# GNSS_MB.net
KiCad netlist of a schematic drawn in Altium Designer
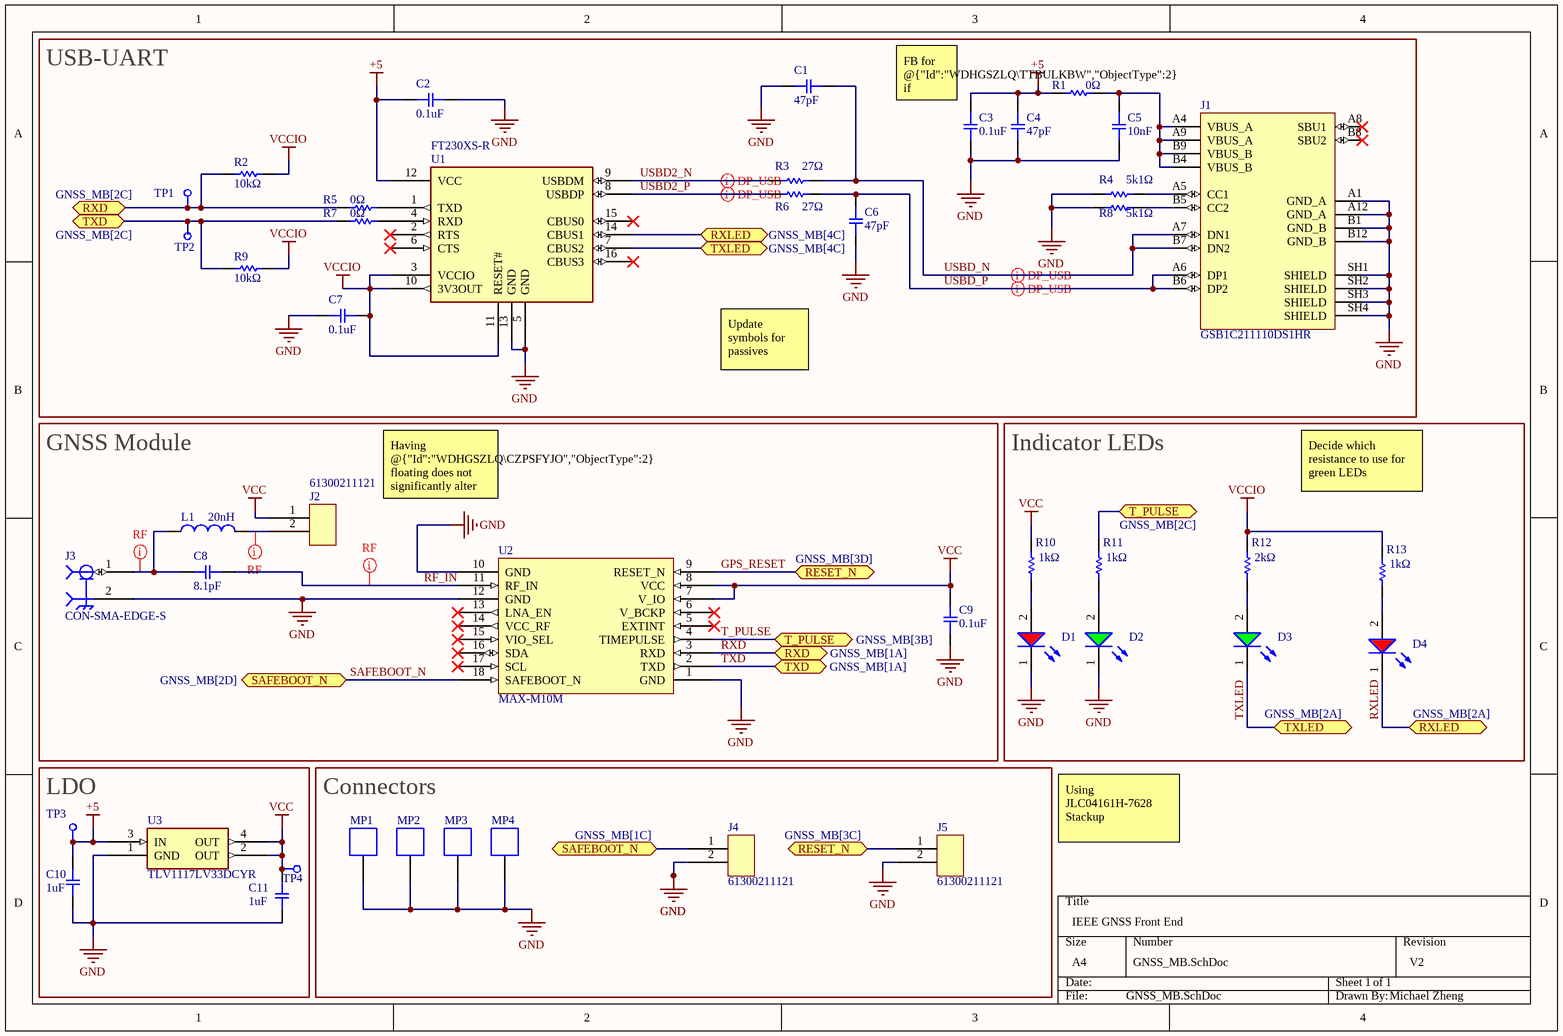
[diagram p0: GNSS_MB.SchDoc]

(export (version "E")
  (design (tool "Eeschema 10.0.6"))
  (components
    (comp (ref "C1")
      (value "GCM1885C2A470JA16D")
      (footprint "CAP_MURATA_0603")
      (description "CAP CER 47PF 100V C0G/NP0 0603")
      (fields (field (name "CAPACITANCE") "47pF"))
      (libsource (lib "Symbols") (part "GCM188L81H104KA57D"))
    )
    (comp (ref "C2")
      (value "GCM188L81H104KA57D")
      (footprint "CAP_MURATA_0603")
      (description "CAP CER 0.1UF 50V X8L 0603")
      (fields (field (name "CAPACITANCE") "0.1uF"))
      (libsource (lib "Symbols") (part "GCM188L81H104KA57D"))
    )
    (comp (ref "C3")
      (value "GCM188L81H104KA57D")
      (footprint "CAP_MURATA_0603")
      (description "CAP CER 0.1UF 50V X8L 0603")
      (fields (field (name "CAPACITANCE") "0.1uF"))
      (libsource (lib "Symbols") (part "GCM188L81H104KA57D"))
    )
    (comp (ref "C4")
      (value "GCM1885C2A470JA16D")
      (footprint "CAP_MURATA_0603")
      (description "CAP CER 47PF 100V C0G/NP0 0603")
      (fields (field (name "CAPACITANCE") "47pF"))
      (libsource (lib "Symbols") (part "GCM188L81H104KA57D"))
    )
    (comp (ref "C5")
      (value "GCM188R72A103KA37D")
      (footprint "CAP_MURATA_0603")
      (description "CAP CER 10000PF 100V X7R 0603")
      (fields (field (name "CAPACITANCE") "10nF"))
      (libsource (lib "Symbols") (part "GCM188L81H104KA57D"))
    )
    (comp (ref "C6")
      (value "GCM1885C2A470JA16D")
      (footprint "CAP_MURATA_0603")
      (description "CAP CER 47PF 100V C0G/NP0 0603")
      (fields (field (name "CAPACITANCE") "47pF"))
      (libsource (lib "Symbols") (part "GCM188L81H104KA57D"))
    )
    (comp (ref "C7")
      (value "GCM188L81H104KA57D")
      (footprint "CAP_MURATA_0603")
      (description "CAP CER 0.1UF 50V X8L 0603")
      (fields (field (name "CAPACITANCE") "0.1uF"))
      (libsource (lib "Symbols") (part "GCM188L81H104KA57D"))
    )
    (comp (ref "C8")
      (value "GJM1555C1H8R1BB01D")
      (footprint "0402_CAP")
      (description "CAP CER 8.1PF 50V C0G/NP0 0402")
      (fields (field (name "CAPACITANCE") "8.1pF"))
      (libsource (lib "Symbols") (part "GRM1555C1H102JA01D"))
    )
    (comp (ref "C9")
      (value "GCM188L81H104KA57D")
      (footprint "CAP_MURATA_0603")
      (description "CAP CER 0.1UF 50V X8L 0603")
      (fields (field (name "CAPACITANCE") "0.1uF"))
      (libsource (lib "Symbols") (part "GCM188L81H104KA57D"))
    )
    (comp (ref "C10")
      (value "GRM188R61A105KA61D")
      (footprint "CAP_MURATA_0603")
      (description "CAP CER 1UF 10V X5R 0603")
      (fields (field (name "CAPACITANCE") "1uF"))
      (libsource (lib "Symbols") (part "GRM188R61A105KA61D"))
    )
    (comp (ref "C11")
      (value "GRM188R61A105KA61D")
      (footprint "CAP_MURATA_0603")
      (description "CAP CER 1UF 10V X5R 0603")
      (fields (field (name "CAPACITANCE") "1uF"))
      (libsource (lib "Symbols") (part "GRM188R61A105KA61D"))
    )
    (comp (ref "D1")
      (value "Red, 2V, 140°")
      (footprint "WL-SMCW")
      (description "WL-SMCW Mono-color Chip LED Waterclear, SMT, size 0603, Red, 2V, 140°")
      (fields
        (field (name "MANUFACTURER PART NUMBER") "150060RS75000")
        (field (name "MANUFACTURER") "Wurth Elektronik")
      )
      (libsource (lib "Symbols") (part "150060RS75000"))
    )
    (comp (ref "D2")
      (value "Green, 3.2V, 140°")
      (footprint "WL-SMCW")
      (description "WL-SMCW Mono-color Chip LED Waterclear, SMT, size 0603, Green, 3.2V, 140°")
      (fields
        (field (name "MANUFACTURER PART NUMBER") "150060GS75000")
        (field (name "MANUFACTURER") "Wurth Elektronik")
      )
      (libsource (lib "Symbols") (part "150060GS75000"))
    )
    (comp (ref "D3")
      (value "Green, 3.2V, 140°")
      (footprint "WL-SMCW")
      (description "WL-SMCW Mono-color Chip LED Waterclear, SMT, size 0603, Green, 3.2V, 140°")
      (fields
        (field (name "MANUFACTURER PART NUMBER") "150060GS75000")
        (field (name "MANUFACTURER") "Wurth Elektronik")
      )
      (libsource (lib "Symbols") (part "150060GS75000"))
    )
    (comp (ref "D4")
      (value "Red, 2V, 140°")
      (footprint "WL-SMCW")
      (description "WL-SMCW Mono-color Chip LED Waterclear, SMT, size 0603, Red, 2V, 140°")
      (fields
        (field (name "MANUFACTURER PART NUMBER") "150060RS75000")
        (field (name "MANUFACTURER") "Wurth Elektronik")
      )
      (libsource (lib "Symbols") (part "150060RS75000"))
    )
    (comp (ref "J1")
      (value "GSB1C211110DS1HR")
      (footprint "AMPHENOL_GSB1C211110DS1HR")
      (description "USB2.0, Type C, Top mount, Center Height 1.78mm, Dual Row DIP")
      (fields (field (name "MF") "Amphenol Canada"))
      (libsource (lib "Symbols") (part "GSB1C211110DS1HR"))
    )
    (comp (ref "J2")
      (value "61300211121")
      (footprint "61300211121")
      (description "CONN HEADER VERT 2POS 2.54MM")
      (libsource (lib "Symbols") (part "61300211121"))
    )
    (comp (ref "J3")
      (value "CON-SMA-EDGE-S")
      (footprint "RFSOLUTIONS_CON-SMA-EDGE-S")
      (description "CONN SMA JACK STR EDGE MNT")
      (libsource (lib "Symbols") (part "CON-SMA-EDGE-S"))
    )
    (comp (ref "J4")
      (value "61300211121")
      (footprint "61300211121")
      (description "CONN HEADER VERT 2POS 2.54MM")
      (libsource (lib "Symbols") (part "61300211121"))
    )
    (comp (ref "J5")
      (value "61300211121")
      (footprint "61300211121")
      (description "CONN HEADER VERT 2POS 2.54MM")
      (libsource (lib "Symbols") (part "61300211121"))
    )
    (comp (ref "L1")
      (value "20nH")
      (footprint "INDC1006X60N")
      (description "FIXED IND 20NH 800MA 0.186OHM SM")
      (fields (field (name "MP") "LQW15AN3N6C10D") (field (name "Comment") "LQW15AN20NG8ZD"))
      (libsource (lib "Symbols") (part "LQW15AN3N6C10D"))
    )
    (comp (ref "MP1")
      (value "36900000")
      (footprint "36900000")
      (description "WE-SHC Shielding Cabinet, Clip, Tin Plated, Tape and Reel, 6.5x0.8x1.27mm")
      (fields (field (name "MANUFACTURER") "Wurth Elektronik"))
      (libsource (lib "Symbols") (part "36900000"))
    )
    (comp (ref "MP2")
      (value "36900000")
      (footprint "36900000")
      (description "WE-SHC Shielding Cabinet, Clip, Tin Plated, Tape and Reel, 6.5x0.8x1.27mm")
      (fields (field (name "MANUFACTURER") "Wurth Elektronik"))
      (libsource (lib "Symbols") (part "36900000"))
    )
    (comp (ref "MP3")
      (value "36900000")
      (footprint "36900000")
      (description "WE-SHC Shielding Cabinet, Clip, Tin Plated, Tape and Reel, 6.5x0.8x1.27mm")
      (fields (field (name "MANUFACTURER") "Wurth Elektronik"))
      (libsource (lib "Symbols") (part "36900000"))
    )
    (comp (ref "MP4")
      (value "36900000")
      (footprint "36900000")
      (description "WE-SHC Shielding Cabinet, Clip, Tin Plated, Tape and Reel, 6.5x0.8x1.27mm")
      (fields (field (name "MANUFACTURER") "Wurth Elektronik"))
      (libsource (lib "Symbols") (part "36900000"))
    )
    (comp (ref "R1")
      (value "RC0603JR-070RL")
      (footprint "RC0603JR-070RL")
      (description "Chip Resistor, 0 Ohm, +/- 5%, 0.1 W, -55 to 155 degC, 0603 (1608 Metric), RoHS, Tape and Reel")
      (fields
        (field (name "TOLERANCE") "5%")
        (field (name "RESISTANCE") "0Ω")
        (field (name "MANUFACTURER") "Yageo")
      )
      (libsource (lib "Symbols") (part "RC0603JR-070RL"))
    )
    (comp (ref "R2")
      (value "RC0603FR-0710KL")
      (footprint "RC0603JR-070RL")
      (description "RES 10K OHM 1% 1/10W 0603")
      (fields
        (field (name "TOLERANCE") "5%")
        (field (name "RESISTANCE") "10kΩ")
        (field (name "MANUFACTURER") "Yageo")
      )
      (libsource (lib "Symbols") (part "RC0603JR-070RL"))
    )
    (comp (ref "R3")
      (value "RC0603FR-0727RL")
      (footprint "RC0603JR-070RL")
      (description "RES 27 OHM 1% 1/10W 0603")
      (fields
        (field (name "TOLERANCE") "5%")
        (field (name "RESISTANCE") "27Ω")
        (field (name "MANUFACTURER") "Yageo")
      )
      (libsource (lib "Symbols") (part "RC0603JR-070RL"))
    )
    (comp (ref "R4")
      (value "RC0603FR-075K1L")
      (footprint "RC0603JR-070RL")
      (description "RES 5.1K OHM 1% 1/10W 0603")
      (fields
        (field (name "TOLERANCE") "5%")
        (field (name "RESISTANCE") "5k1Ω")
        (field (name "MANUFACTURER") "Yageo")
      )
      (libsource (lib "Symbols") (part "RC0603JR-070RL"))
    )
    (comp (ref "R5")
      (value "RC0603JR-070RL")
      (footprint "RC0603JR-070RL")
      (description "Chip Resistor, 0 Ohm, +/- 5%, 0.1 W, -55 to 155 degC, 0603 (1608 Metric), RoHS, Tape and Reel")
      (fields
        (field (name "TOLERANCE") "5%")
        (field (name "RESISTANCE") "0Ω")
        (field (name "MANUFACTURER") "Yageo")
      )
      (libsource (lib "Symbols") (part "RC0603JR-070RL"))
    )
    (comp (ref "R6")
      (value "RC0603FR-0727RL")
      (footprint "RC0603JR-070RL")
      (description "RES 27 OHM 1% 1/10W 0603")
      (fields
        (field (name "TOLERANCE") "5%")
        (field (name "RESISTANCE") "27Ω")
        (field (name "MANUFACTURER") "Yageo")
      )
      (libsource (lib "Symbols") (part "RC0603JR-070RL"))
    )
    (comp (ref "R7")
      (value "RC0603JR-070RL")
      (footprint "RC0603JR-070RL")
      (description "Chip Resistor, 0 Ohm, +/- 5%, 0.1 W, -55 to 155 degC, 0603 (1608 Metric), RoHS, Tape and Reel")
      (fields
        (field (name "TOLERANCE") "5%")
        (field (name "RESISTANCE") "0Ω")
        (field (name "MANUFACTURER") "Yageo")
      )
      (libsource (lib "Symbols") (part "RC0603JR-070RL"))
    )
    (comp (ref "R8")
      (value "RC0603FR-075K1L")
      (footprint "RC0603JR-070RL")
      (description "RES 5.1K OHM 1% 1/10W 0603")
      (fields
        (field (name "TOLERANCE") "5%")
        (field (name "RESISTANCE") "5k1Ω")
        (field (name "MANUFACTURER") "Yageo")
      )
      (libsource (lib "Symbols") (part "RC0603JR-070RL"))
    )
    (comp (ref "R9")
      (value "RC0603FR-0710KL")
      (footprint "RC0603JR-070RL")
      (description "RES 10K OHM 1% 1/10W 0603")
      (fields
        (field (name "TOLERANCE") "5%")
        (field (name "RESISTANCE") "10kΩ")
        (field (name "MANUFACTURER") "Yageo")
      )
      (libsource (lib "Symbols") (part "RC0603JR-070RL"))
    )
    (comp (ref "R10")
      (value "RC0603FR-071KL")
      (footprint "RC0603JR-070RL")
      (description "1 kOhms ±1% 0.1W, 1/10W Chip Resistor 0603 (1608 Metric) Moisture Resistant Thick Film")
      (fields
        (field (name "TOLERANCE") "5%")
        (field (name "RESISTANCE") "1kΩ")
        (field (name "MANUFACTURER") "Yageo")
      )
      (libsource (lib "Symbols") (part "RC0603JR-070RL"))
    )
    (comp (ref "R11")
      (value "RC0603FR-071KL")
      (footprint "RC0603JR-070RL")
      (description "1 kOhms ±1% 0.1W, 1/10W Chip Resistor 0603 (1608 Metric) Moisture Resistant Thick Film")
      (fields
        (field (name "TOLERANCE") "5%")
        (field (name "RESISTANCE") "1kΩ")
        (field (name "MANUFACTURER") "Yageo")
      )
      (libsource (lib "Symbols") (part "RC0603JR-070RL"))
    )
    (comp (ref "R12")
      (value "RC0603JR-072KL")
      (footprint "RC0603JR-070RL")
      (description "2 kOhms ±5% 0.1W, 1/10W Chip Resistor 0603 (1608 Metric) Moisture Resistant Thick Film")
      (fields
        (field (name "TOLERANCE") "5%")
        (field (name "RESISTANCE") "2kΩ")
        (field (name "MANUFACTURER") "Yageo")
      )
      (libsource (lib "Symbols") (part "RC0603JR-070RL"))
    )
    (comp (ref "R13")
      (value "RC0603FR-071KL")
      (footprint "RC0603JR-070RL")
      (description "1 kOhms ±1% 0.1W, 1/10W Chip Resistor 0603 (1608 Metric) Moisture Resistant Thick Film")
      (fields
        (field (name "TOLERANCE") "5%")
        (field (name "RESISTANCE") "1kΩ")
        (field (name "MANUFACTURER") "Yageo")
      )
      (libsource (lib "Symbols") (part "RC0603JR-070RL"))
    )
    (comp (ref "TP1")
      (value "TEST_POINT")
      (footprint "TEST_POINT")
      (description "TEST POINT 2MM")
      (libsource (lib "Symbols") (part "TEST_POINT"))
    )
    (comp (ref "TP2")
      (value "TEST_POINT")
      (footprint "TEST_POINT")
      (description "TEST POINT 2MM")
      (libsource (lib "Symbols") (part "TEST_POINT"))
    )
    (comp (ref "TP3")
      (value "TEST_POINT")
      (footprint "TEST_POINT")
      (description "TEST POINT 2MM")
      (libsource (lib "Symbols") (part "TEST_POINT"))
    )
    (comp (ref "TP4")
      (value "TEST_POINT")
      (footprint "TEST_POINT")
      (description "TEST POINT 2MM")
      (libsource (lib "Symbols") (part "TEST_POINT"))
    )
    (comp (ref "U1")
      (value "FT230XS-R")
      (footprint "FT230XS-R")
      (description "USB FULL SPEED TO SERIAL UART IC")
      (libsource (lib "Symbols") (part "FT230XS-R"))
    )
    (comp (ref "U2")
      (value "MAX-M10M")
      (footprint "MAX-M10M")
      (description "GNSS LCC RX MOD, ROM, CRYSTAL")
      (libsource (lib "Symbols") (part "MAX-M10M"))
    )
    (comp (ref "U3")
      (value "TLV1117LV33DCYR")
      (footprint "TLV1117LV33DCYR")
      (description "IC REG LINEAR 3.3V 1A SOT223-4")
      (libsource (lib "Symbols") (part "TLV1117LV33DCYR"))
    )
  )
  (nets
    (net (code "1") (name "+5") (class "Default")
      (node (ref "C10") (pin "2") (pinfunction "2_2") (pintype "passive"))
      (node (ref "C2") (pin "2") (pinfunction "2_2") (pintype "passive"))
      (node (ref "C3") (pin "1") (pinfunction "1_1") (pintype "passive"))
      (node (ref "C4") (pin "1") (pinfunction "1_1") (pintype "passive"))
      (node (ref "R1") (pin "1") (pinfunction "1_1") (pintype "passive"))
      (node (ref "TP3") (pin "1") (pinfunction "1_1") (pintype "passive"))
      (node (ref "U1") (pin "12") (pinfunction "VCC_12") (pintype "power_in"))
      (node (ref "U3") (pin "3") (pinfunction "IN_3") (pintype "input"))
    )
    (net (code "2") (name "/GPS_RESET") (class "Default")
      (node (ref "J5") (pin "1") (pintype "passive"))
      (node (ref "U2") (pin "9") (pinfunction "RESET_N_9") (pintype "input"))
    )
    (net (code "3") (name "/RF_IN") (class "Default")
      (node (ref "C8") (pin "2") (pinfunction "2_2") (pintype "passive"))
      (node (ref "U2") (pin "11") (pinfunction "RF_IN_11") (pintype "input"))
    )
    (net (code "4") (name "/RXD") (class "Default")
      (node (ref "R2") (pin "1") (pinfunction "1_1") (pintype "passive"))
      (node (ref "R5") (pin "1") (pinfunction "1_1") (pintype "passive"))
      (node (ref "TP1") (pin "1") (pinfunction "1_1") (pintype "passive"))
      (node (ref "U2") (pin "3") (pinfunction "RXD_3") (pintype "input"))
    )
    (net (code "5") (name "/RXLED") (class "Default")
      (node (ref "D4") (pin "1") (pinfunction "K_1") (pintype "passive"))
      (node (ref "U1") (pin "14") (pinfunction "CBUS1_14") (pintype "bidirectional"))
    )
    (net (code "6") (name "/SAFEBOOT_N") (class "Default")
      (node (ref "J4") (pin "1") (pintype "passive"))
      (node (ref "U2") (pin "18") (pinfunction "SAFEBOOT_N_18") (pintype "input"))
    )
    (net (code "7") (name "/TXD") (class "Default")
      (node (ref "R7") (pin "1") (pinfunction "1_1") (pintype "passive"))
      (node (ref "R9") (pin "1") (pinfunction "1_1") (pintype "passive"))
      (node (ref "TP2") (pin "1") (pinfunction "1_1") (pintype "passive"))
      (node (ref "U2") (pin "2") (pinfunction "TXD_2") (pintype "output"))
    )
    (net (code "8") (name "/TXLED") (class "Default")
      (node (ref "D3") (pin "1") (pinfunction "K_1") (pintype "passive"))
      (node (ref "U1") (pin "7") (pinfunction "CBUS2_7") (pintype "bidirectional"))
    )
    (net (code "9") (name "/T_PULSE") (class "Default")
      (node (ref "R11") (pin "2") (pinfunction "2_2") (pintype "passive"))
      (node (ref "U2") (pin "4") (pinfunction "TIMEPULSE_4") (pintype "output"))
    )
    (net (code "10") (name "/USBD2_N") (class "Default")
      (node (ref "R3") (pin "1") (pinfunction "1_1") (pintype "passive"))
      (node (ref "U1") (pin "9") (pinfunction "USBDM_9") (pintype "bidirectional"))
    )
    (net (code "11") (name "/USBD2_P") (class "Default")
      (node (ref "R6") (pin "1") (pinfunction "1_1") (pintype "passive"))
      (node (ref "U1") (pin "8") (pinfunction "USBDP_8") (pintype "bidirectional"))
    )
    (net (code "12") (name "/USBD_N") (class "Default")
      (node (ref "C1") (pin "2") (pinfunction "2_2") (pintype "passive"))
      (node (ref "J1") (pin "A7") (pinfunction "DN1_A7") (pintype "bidirectional"))
      (node (ref "J1") (pin "B7") (pinfunction "DN2_B7") (pintype "bidirectional"))
      (node (ref "R3") (pin "2") (pinfunction "2_2") (pintype "passive"))
    )
    (net (code "13") (name "/USBD_P") (class "Default")
      (node (ref "C6") (pin "1") (pinfunction "1_1") (pintype "passive"))
      (node (ref "J1") (pin "A6") (pinfunction "DP1_A6") (pintype "bidirectional"))
      (node (ref "J1") (pin "B6") (pinfunction "DP2_B6") (pintype "bidirectional"))
      (node (ref "R6") (pin "2") (pinfunction "2_2") (pintype "passive"))
    )
    (net (code "14") (name "GND") (class "Default")
      (node (ref "C1") (pin "1") (pinfunction "1_1") (pintype "passive"))
      (node (ref "C10") (pin "1") (pinfunction "1_1") (pintype "passive"))
      (node (ref "C11") (pin "1") (pinfunction "1_1") (pintype "passive"))
      (node (ref "C2") (pin "1") (pinfunction "1_1") (pintype "passive"))
      (node (ref "C3") (pin "2") (pinfunction "2_2") (pintype "passive"))
      (node (ref "C4") (pin "2") (pinfunction "2_2") (pintype "passive"))
      (node (ref "C5") (pin "2") (pinfunction "2_2") (pintype "passive"))
      (node (ref "C6") (pin "2") (pinfunction "2_2") (pintype "passive"))
      (node (ref "C7") (pin "2") (pinfunction "2_2") (pintype "passive"))
      (node (ref "C9") (pin "1") (pinfunction "1_1") (pintype "passive"))
      (node (ref "D1") (pin "1") (pinfunction "K_1") (pintype "passive"))
      (node (ref "D2") (pin "1") (pinfunction "K_1") (pintype "passive"))
      (node (ref "J1") (pin "A1") (pinfunction "GND_A_A1") (pintype "power_in"))
      (node (ref "J1") (pin "A12") (pinfunction "GND_A_A12") (pintype "power_in"))
      (node (ref "J1") (pin "B1") (pinfunction "GND_B_B1") (pintype "power_in"))
      (node (ref "J1") (pin "B12") (pinfunction "GND_B_B12") (pintype "power_in"))
      (node (ref "J1") (pin "SH1") (pinfunction "SHIELD_SH1") (pintype "passive"))
      (node (ref "J1") (pin "SH2") (pinfunction "SHIELD_SH2") (pintype "passive"))
      (node (ref "J1") (pin "SH3") (pinfunction "SHIELD_SH3") (pintype "passive"))
      (node (ref "J1") (pin "SH4") (pinfunction "SHIELD_SH4") (pintype "passive"))
      (node (ref "J3") (pin "2") (pinfunction "GND_2") (pintype "power_in"))
      (node (ref "J4") (pin "2") (pintype "passive"))
      (node (ref "J5") (pin "2") (pintype "passive"))
      (node (ref "MP1") (pin "1") (pinfunction "1_1") (pintype "passive"))
      (node (ref "MP2") (pin "1") (pinfunction "1_1") (pintype "passive"))
      (node (ref "MP3") (pin "1") (pinfunction "1_1") (pintype "passive"))
      (node (ref "MP4") (pin "1") (pinfunction "1_1") (pintype "passive"))
      (node (ref "R4") (pin "1") (pinfunction "1_1") (pintype "passive"))
      (node (ref "R8") (pin "1") (pinfunction "1_1") (pintype "passive"))
      (node (ref "U1") (pin "13") (pinfunction "GND_13") (pintype "power_in"))
      (node (ref "U1") (pin "5") (pinfunction "GND_5") (pintype "power_in"))
      (node (ref "U2") (pin "1") (pinfunction "GND_1") (pintype "power_in"))
      (node (ref "U2") (pin "10") (pinfunction "GND_10") (pintype "power_in"))
      (node (ref "U2") (pin "12") (pinfunction "GND_12") (pintype "power_in"))
      (node (ref "U3") (pin "1") (pinfunction "GND_1") (pintype "power_in"))
    )
    (net (code "15") (name "Net-(C5-Pad1)") (class "Default")
      (node (ref "C5") (pin "1") (pinfunction "1_1") (pintype "passive"))
      (node (ref "J1") (pin "A4") (pinfunction "VBUS_A_A4") (pintype "power_in"))
      (node (ref "J1") (pin "A9") (pinfunction "VBUS_A_A9") (pintype "power_in"))
      (node (ref "J1") (pin "B4") (pinfunction "VBUS_B_B4") (pintype "power_in"))
      (node (ref "J1") (pin "B9") (pinfunction "VBUS_B_B9") (pintype "power_in"))
      (node (ref "R1") (pin "2") (pinfunction "2_2") (pintype "passive"))
    )
    (net (code "16") (name "Net-(D1-A)") (class "Default")
      (node (ref "D1") (pin "2") (pinfunction "A_2") (pintype "passive"))
      (node (ref "R10") (pin "1") (pinfunction "1_1") (pintype "passive"))
    )
    (net (code "17") (name "Net-(D2-A)") (class "Default")
      (node (ref "D2") (pin "2") (pinfunction "A_2") (pintype "passive"))
      (node (ref "R11") (pin "1") (pinfunction "1_1") (pintype "passive"))
    )
    (net (code "18") (name "Net-(D3-A)") (class "Default")
      (node (ref "D3") (pin "2") (pinfunction "A_2") (pintype "passive"))
      (node (ref "R12") (pin "1") (pinfunction "1_1") (pintype "passive"))
    )
    (net (code "19") (name "Net-(D4-A)") (class "Default")
      (node (ref "D4") (pin "2") (pinfunction "A_2") (pintype "passive"))
      (node (ref "R13") (pin "1") (pinfunction "1_1") (pintype "passive"))
    )
    (net (code "20") (name "Net-(J1-CC1)") (class "Default")
      (node (ref "J1") (pin "A5") (pinfunction "CC1_A5") (pintype "bidirectional"))
      (node (ref "R4") (pin "2") (pinfunction "2_2") (pintype "passive"))
    )
    (net (code "21") (name "Net-(J1-CC2)") (class "Default")
      (node (ref "J1") (pin "B5") (pinfunction "CC2_B5") (pintype "bidirectional"))
      (node (ref "R8") (pin "2") (pinfunction "2_2") (pintype "passive"))
    )
    (net (code "22") (name "Net-(J2-Pad2)") (class "Default")
      (node (ref "J2") (pin "2") (pintype "passive"))
      (node (ref "L1") (pin "2") (pinfunction "2_2") (pintype "passive"))
    )
    (net (code "23") (name "Net-(J3-RF)") (class "Default")
      (node (ref "C8") (pin "1") (pinfunction "1_1") (pintype "passive"))
      (node (ref "J3") (pin "1") (pinfunction "RF_1") (pintype "bidirectional"))
      (node (ref "L1") (pin "1") (pinfunction "1_1") (pintype "passive"))
    )
    (net (code "24") (name "Net-(U1-RXD)") (class "Default")
      (node (ref "R7") (pin "2") (pinfunction "2_2") (pintype "passive"))
      (node (ref "U1") (pin "4") (pinfunction "RXD_4") (pintype "input"))
    )
    (net (code "25") (name "Net-(U1-TXD)") (class "Default")
      (node (ref "R5") (pin "2") (pinfunction "2_2") (pintype "passive"))
      (node (ref "U1") (pin "1") (pinfunction "TXD_1") (pintype "output"))
    )
    (net (code "26") (name "VCC") (class "Default")
      (node (ref "C11") (pin "2") (pinfunction "2_2") (pintype "passive"))
      (node (ref "C9") (pin "2") (pinfunction "2_2") (pintype "passive"))
      (node (ref "J2") (pin "1") (pintype "passive"))
      (node (ref "R10") (pin "2") (pinfunction "2_2") (pintype "passive"))
      (node (ref "TP4") (pin "1") (pinfunction "1_1") (pintype "passive"))
      (node (ref "U2") (pin "7") (pinfunction "V_IO_7") (pintype "input"))
      (node (ref "U2") (pin "8") (pinfunction "VCC_8") (pintype "input"))
      (node (ref "U3") (pin "2") (pinfunction "OUT_2") (pintype "output"))
      (node (ref "U3") (pin "4") (pinfunction "OUT_4") (pintype "output"))
    )
    (net (code "27") (name "VCCIO") (class "Default")
      (node (ref "C7") (pin "1") (pinfunction "1_1") (pintype "passive"))
      (node (ref "R12") (pin "2") (pinfunction "2_2") (pintype "passive"))
      (node (ref "R13") (pin "2") (pinfunction "2_2") (pintype "passive"))
      (node (ref "R2") (pin "2") (pinfunction "2_2") (pintype "passive"))
      (node (ref "R9") (pin "2") (pinfunction "2_2") (pintype "passive"))
      (node (ref "U1") (pin "10") (pinfunction "3V3OUT_10") (pintype "output"))
      (node (ref "U1") (pin "11") (pinfunction "RESET#_11") (pintype "power_in"))
      (node (ref "U1") (pin "3") (pinfunction "VCCIO_3") (pintype "power_in"))
    )
    (net (code "28") (name "unconnected-(J1-SBU1-PadA8)") (class "Default")
      (node (ref "J1") (pin "A8") (pinfunction "SBU1_A8") (pintype "bidirectional+no_connect"))
    )
    (net (code "29") (name "unconnected-(J1-SBU2-PadB8)") (class "Default")
      (node (ref "J1") (pin "B8") (pinfunction "SBU2_B8") (pintype "bidirectional+no_connect"))
    )
    (net (code "30") (name "unconnected-(U1-CBUS0-Pad15)") (class "Default")
      (node (ref "U1") (pin "15") (pinfunction "CBUS0_15") (pintype "bidirectional+no_connect"))
    )
    (net (code "31") (name "unconnected-(U1-CBUS3-Pad16)") (class "Default")
      (node (ref "U1") (pin "16") (pinfunction "CBUS3_16") (pintype "bidirectional+no_connect"))
    )
    (net (code "32") (name "unconnected-(U1-CTS-Pad6)") (class "Default")
      (node (ref "U1") (pin "6") (pinfunction "CTS_6") (pintype "input+no_connect"))
    )
    (net (code "33") (name "unconnected-(U1-RTS-Pad2)") (class "Default")
      (node (ref "U1") (pin "2") (pinfunction "RTS_2") (pintype "output+no_connect"))
    )
    (net (code "34") (name "unconnected-(U2-EXTINT-Pad5)") (class "Default")
      (node (ref "U2") (pin "5") (pinfunction "EXTINT_5") (pintype "input+no_connect"))
    )
    (net (code "35") (name "unconnected-(U2-LNA_EN-Pad13)") (class "Default")
      (node (ref "U2") (pin "13") (pinfunction "LNA_EN_13") (pintype "output+no_connect"))
    )
    (net (code "36") (name "unconnected-(U2-SCL-Pad17)") (class "Default")
      (node (ref "U2") (pin "17") (pinfunction "SCL_17") (pintype "input+no_connect"))
    )
    (net (code "37") (name "unconnected-(U2-SDA-Pad16)") (class "Default")
      (node (ref "U2") (pin "16") (pinfunction "SDA_16") (pintype "bidirectional+no_connect"))
    )
    (net (code "38") (name "unconnected-(U2-VCC_RF-Pad14)") (class "Default")
      (node (ref "U2") (pin "14") (pinfunction "VCC_RF_14") (pintype "output+no_connect"))
    )
    (net (code "39") (name "unconnected-(U2-VIO_SEL-Pad15)") (class "Default")
      (node (ref "U2") (pin "15") (pinfunction "VIO_SEL_15") (pintype "input+no_connect"))
    )
    (net (code "40") (name "unconnected-(U2-V_BCKP-Pad6)") (class "Default")
      (node (ref "U2") (pin "6") (pinfunction "V_BCKP_6") (pintype "input+no_connect"))
    )
  )
)
